# mote_cc3200v7.net
KiCad netlist of a schematic drawn in EAGLE
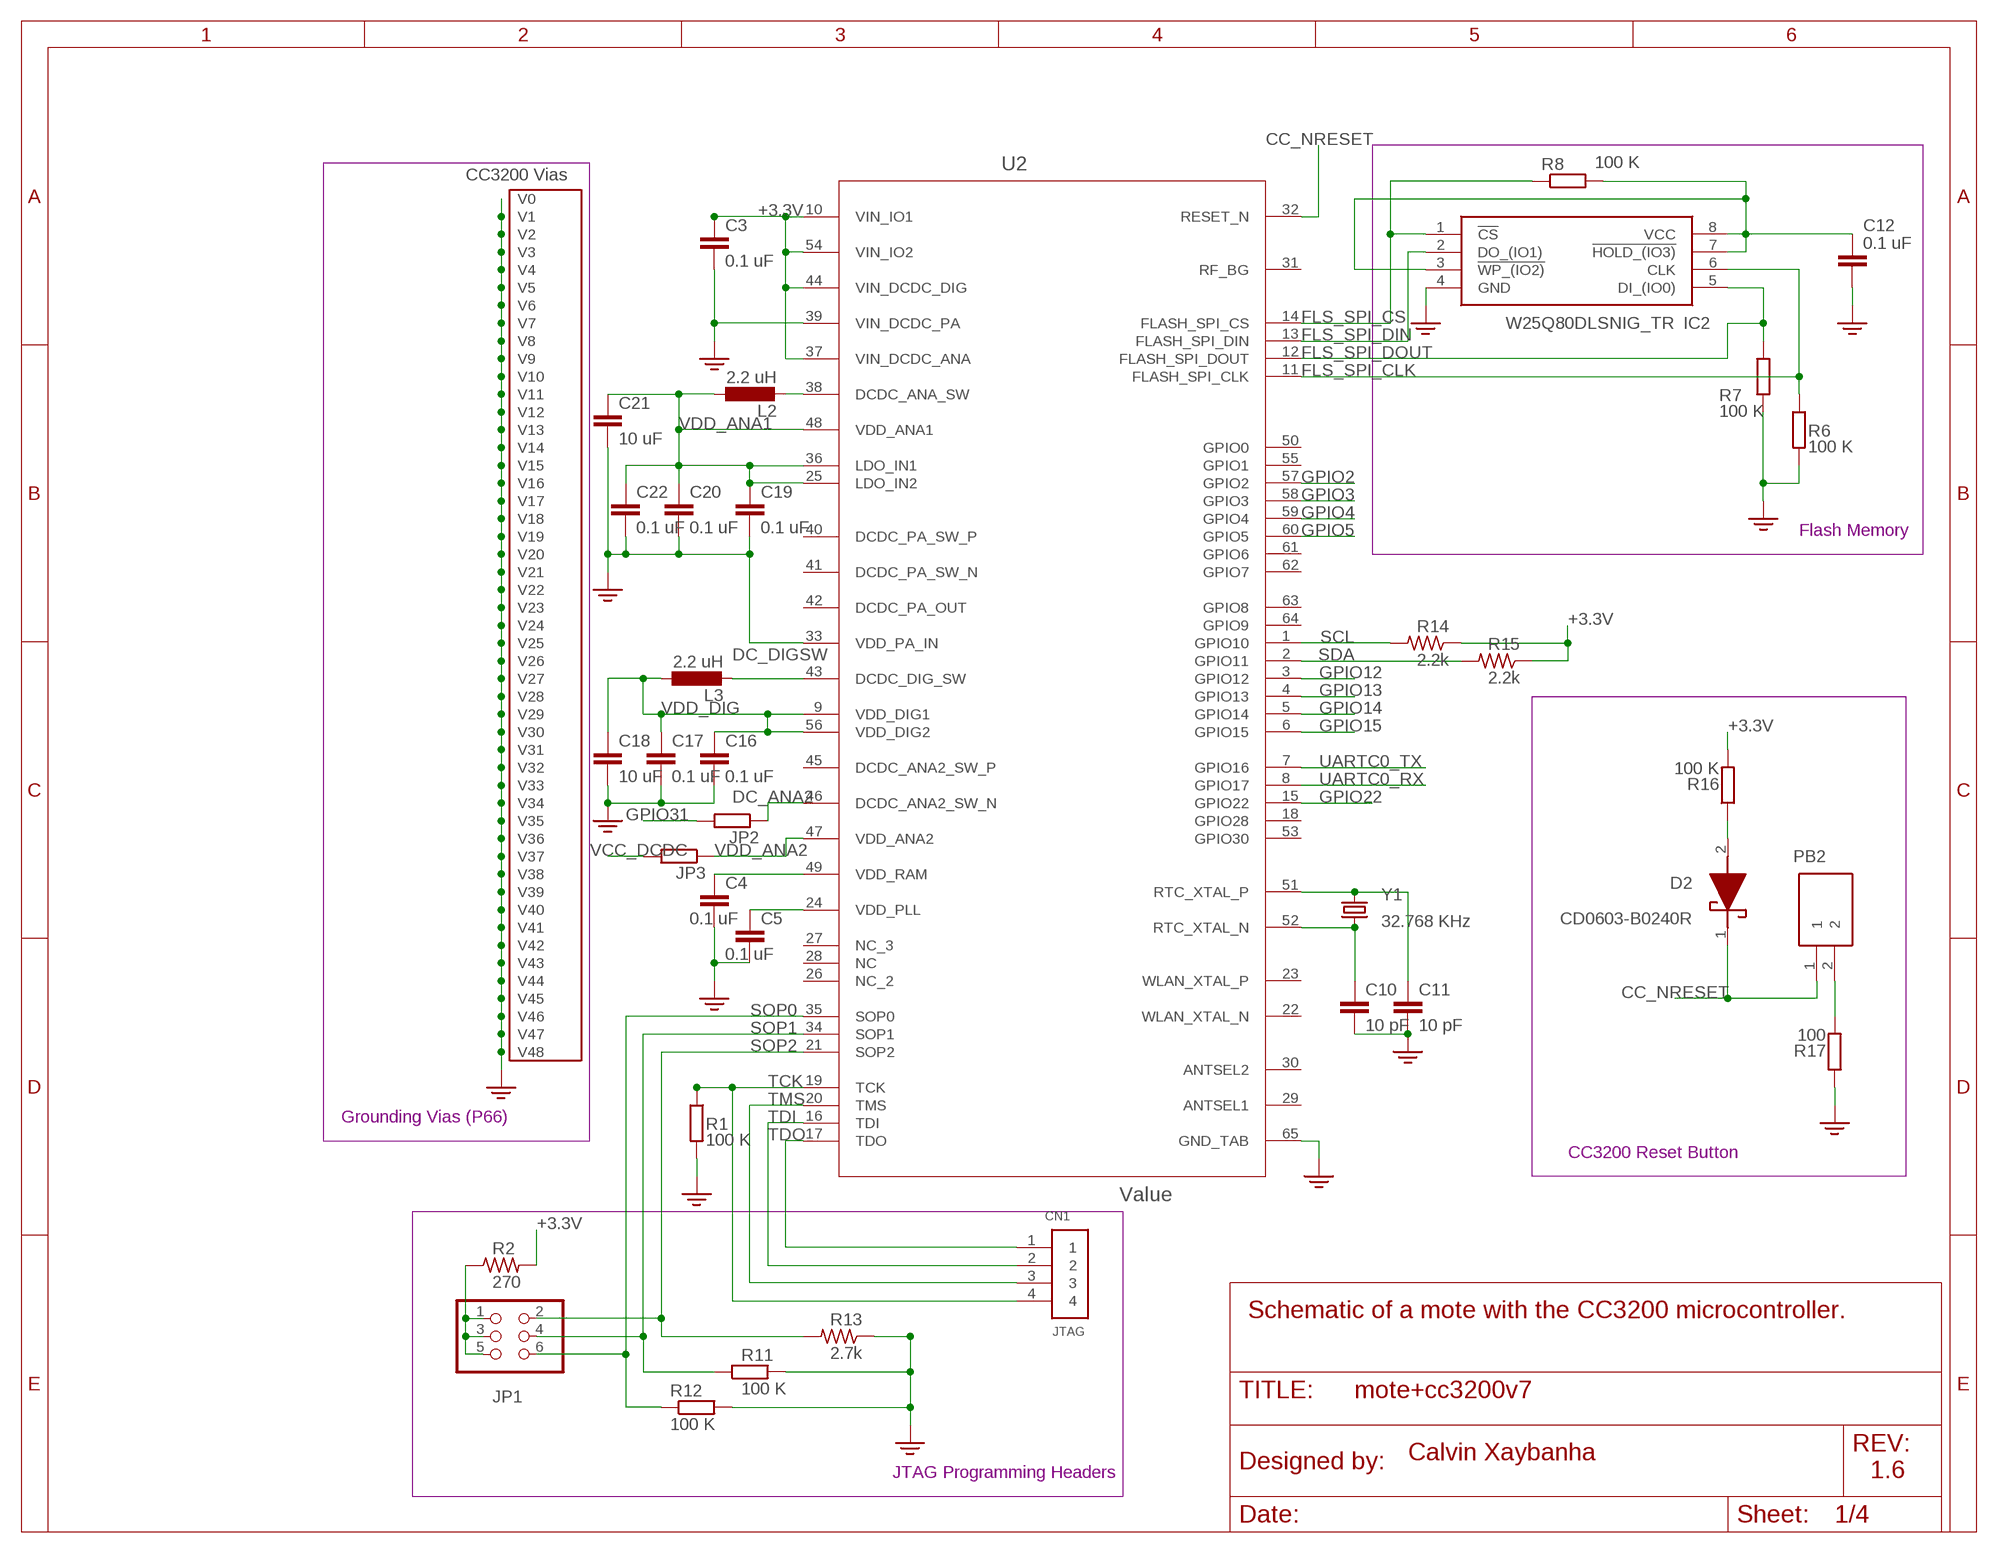
[diagram p0: schematic, sheet 1]
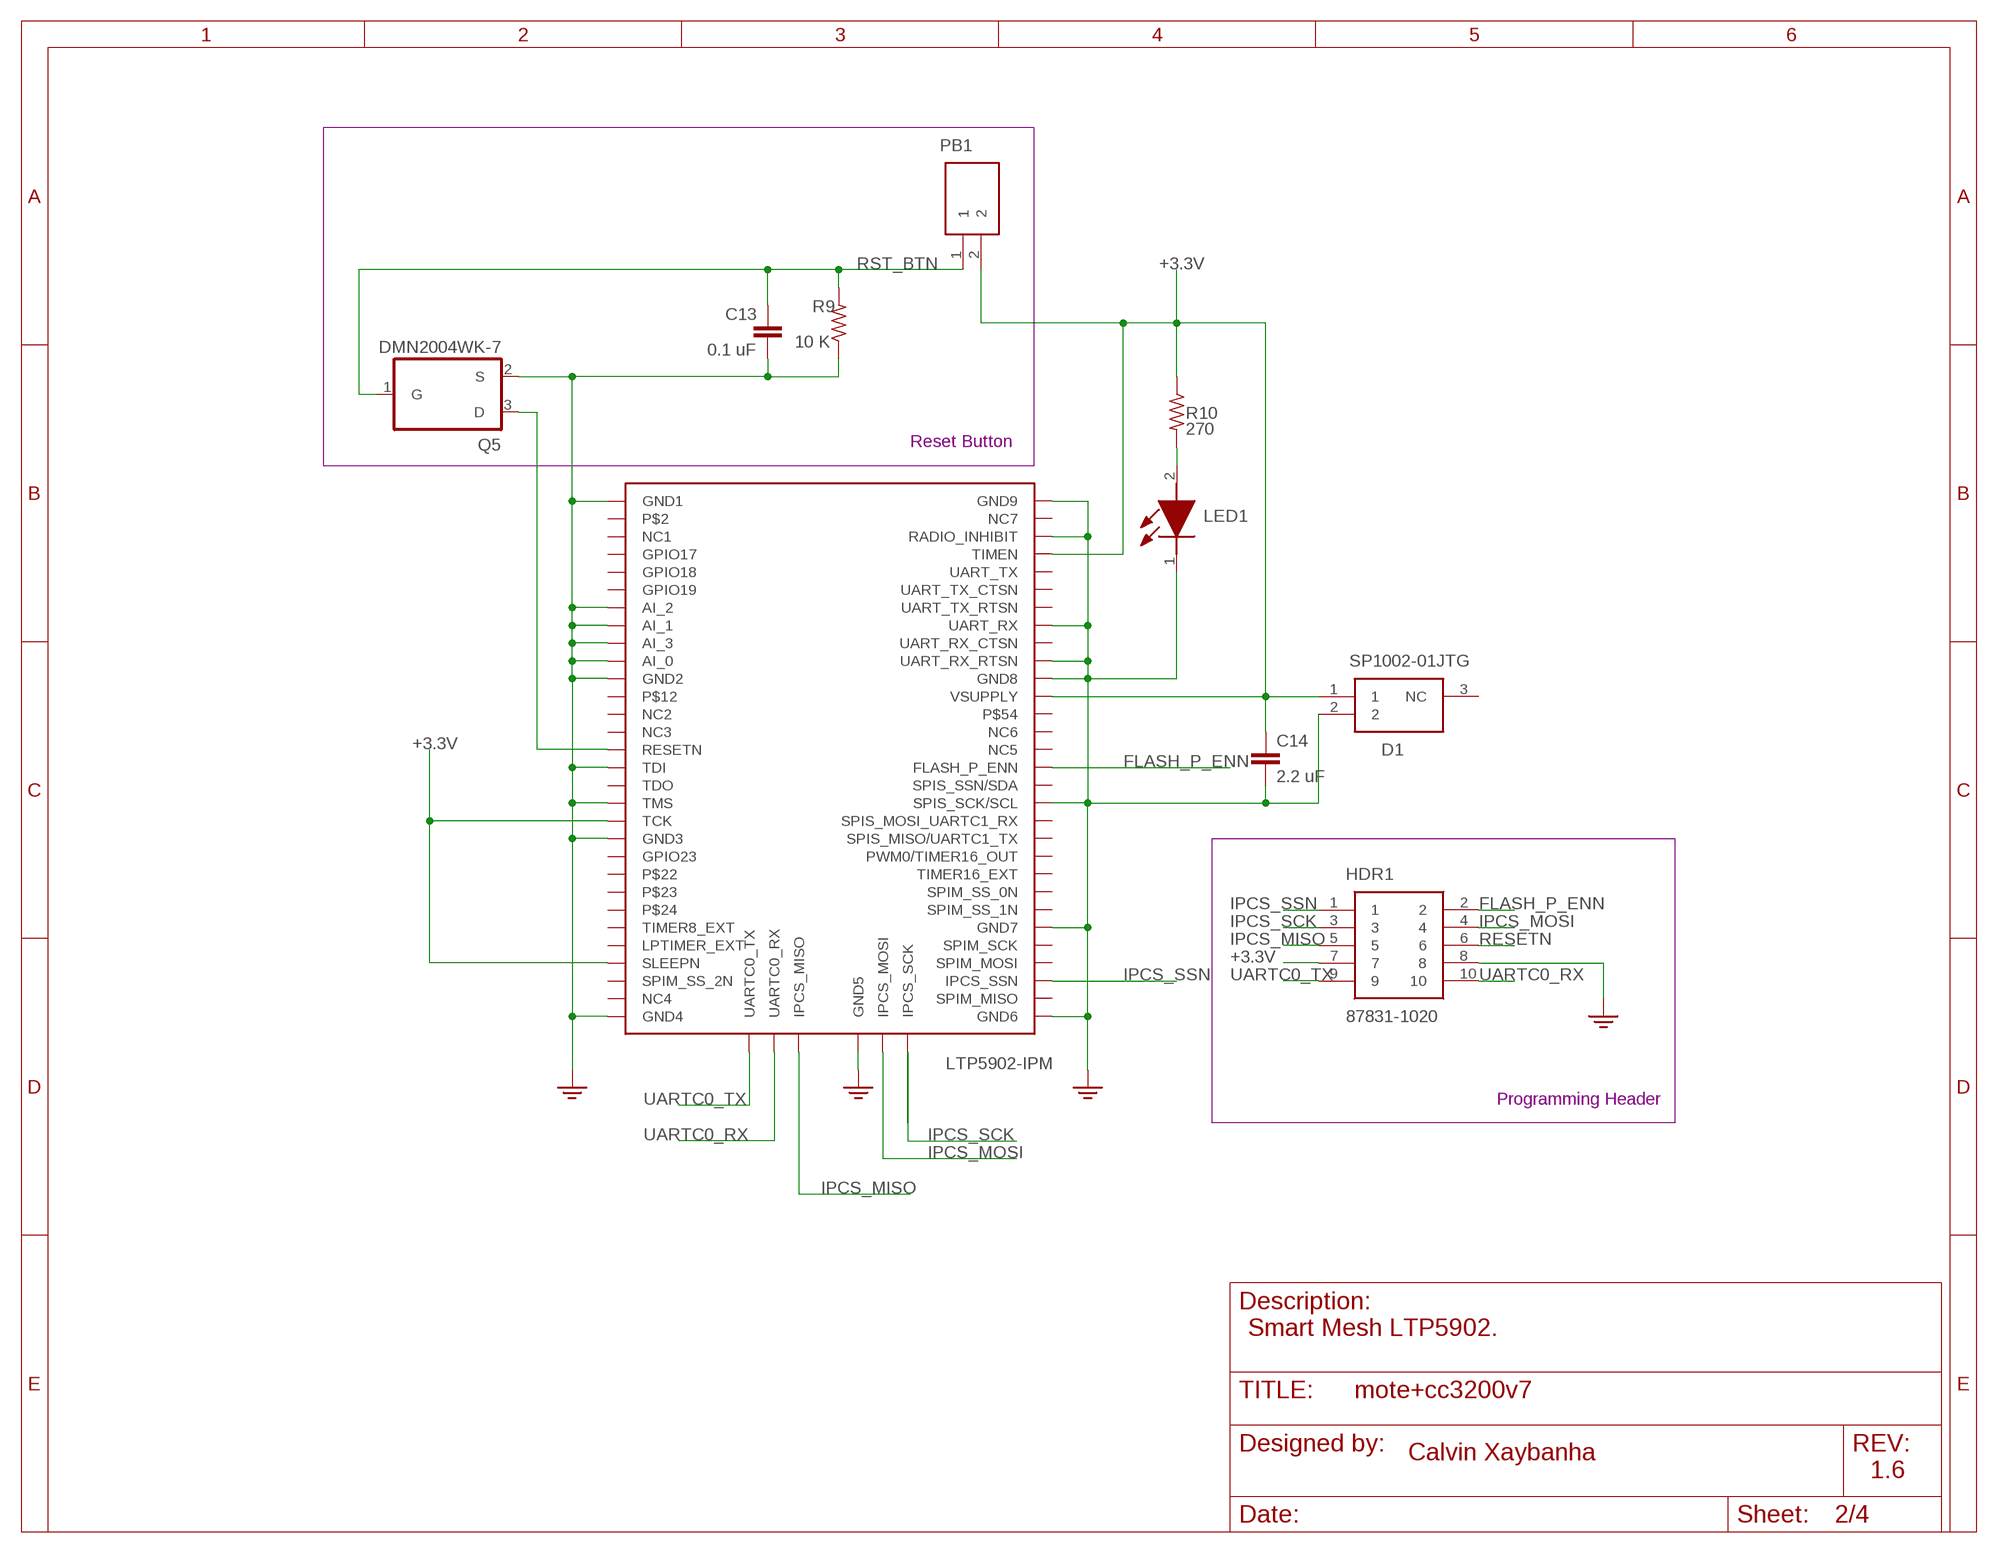
[diagram p1: schematic, sheet 2]
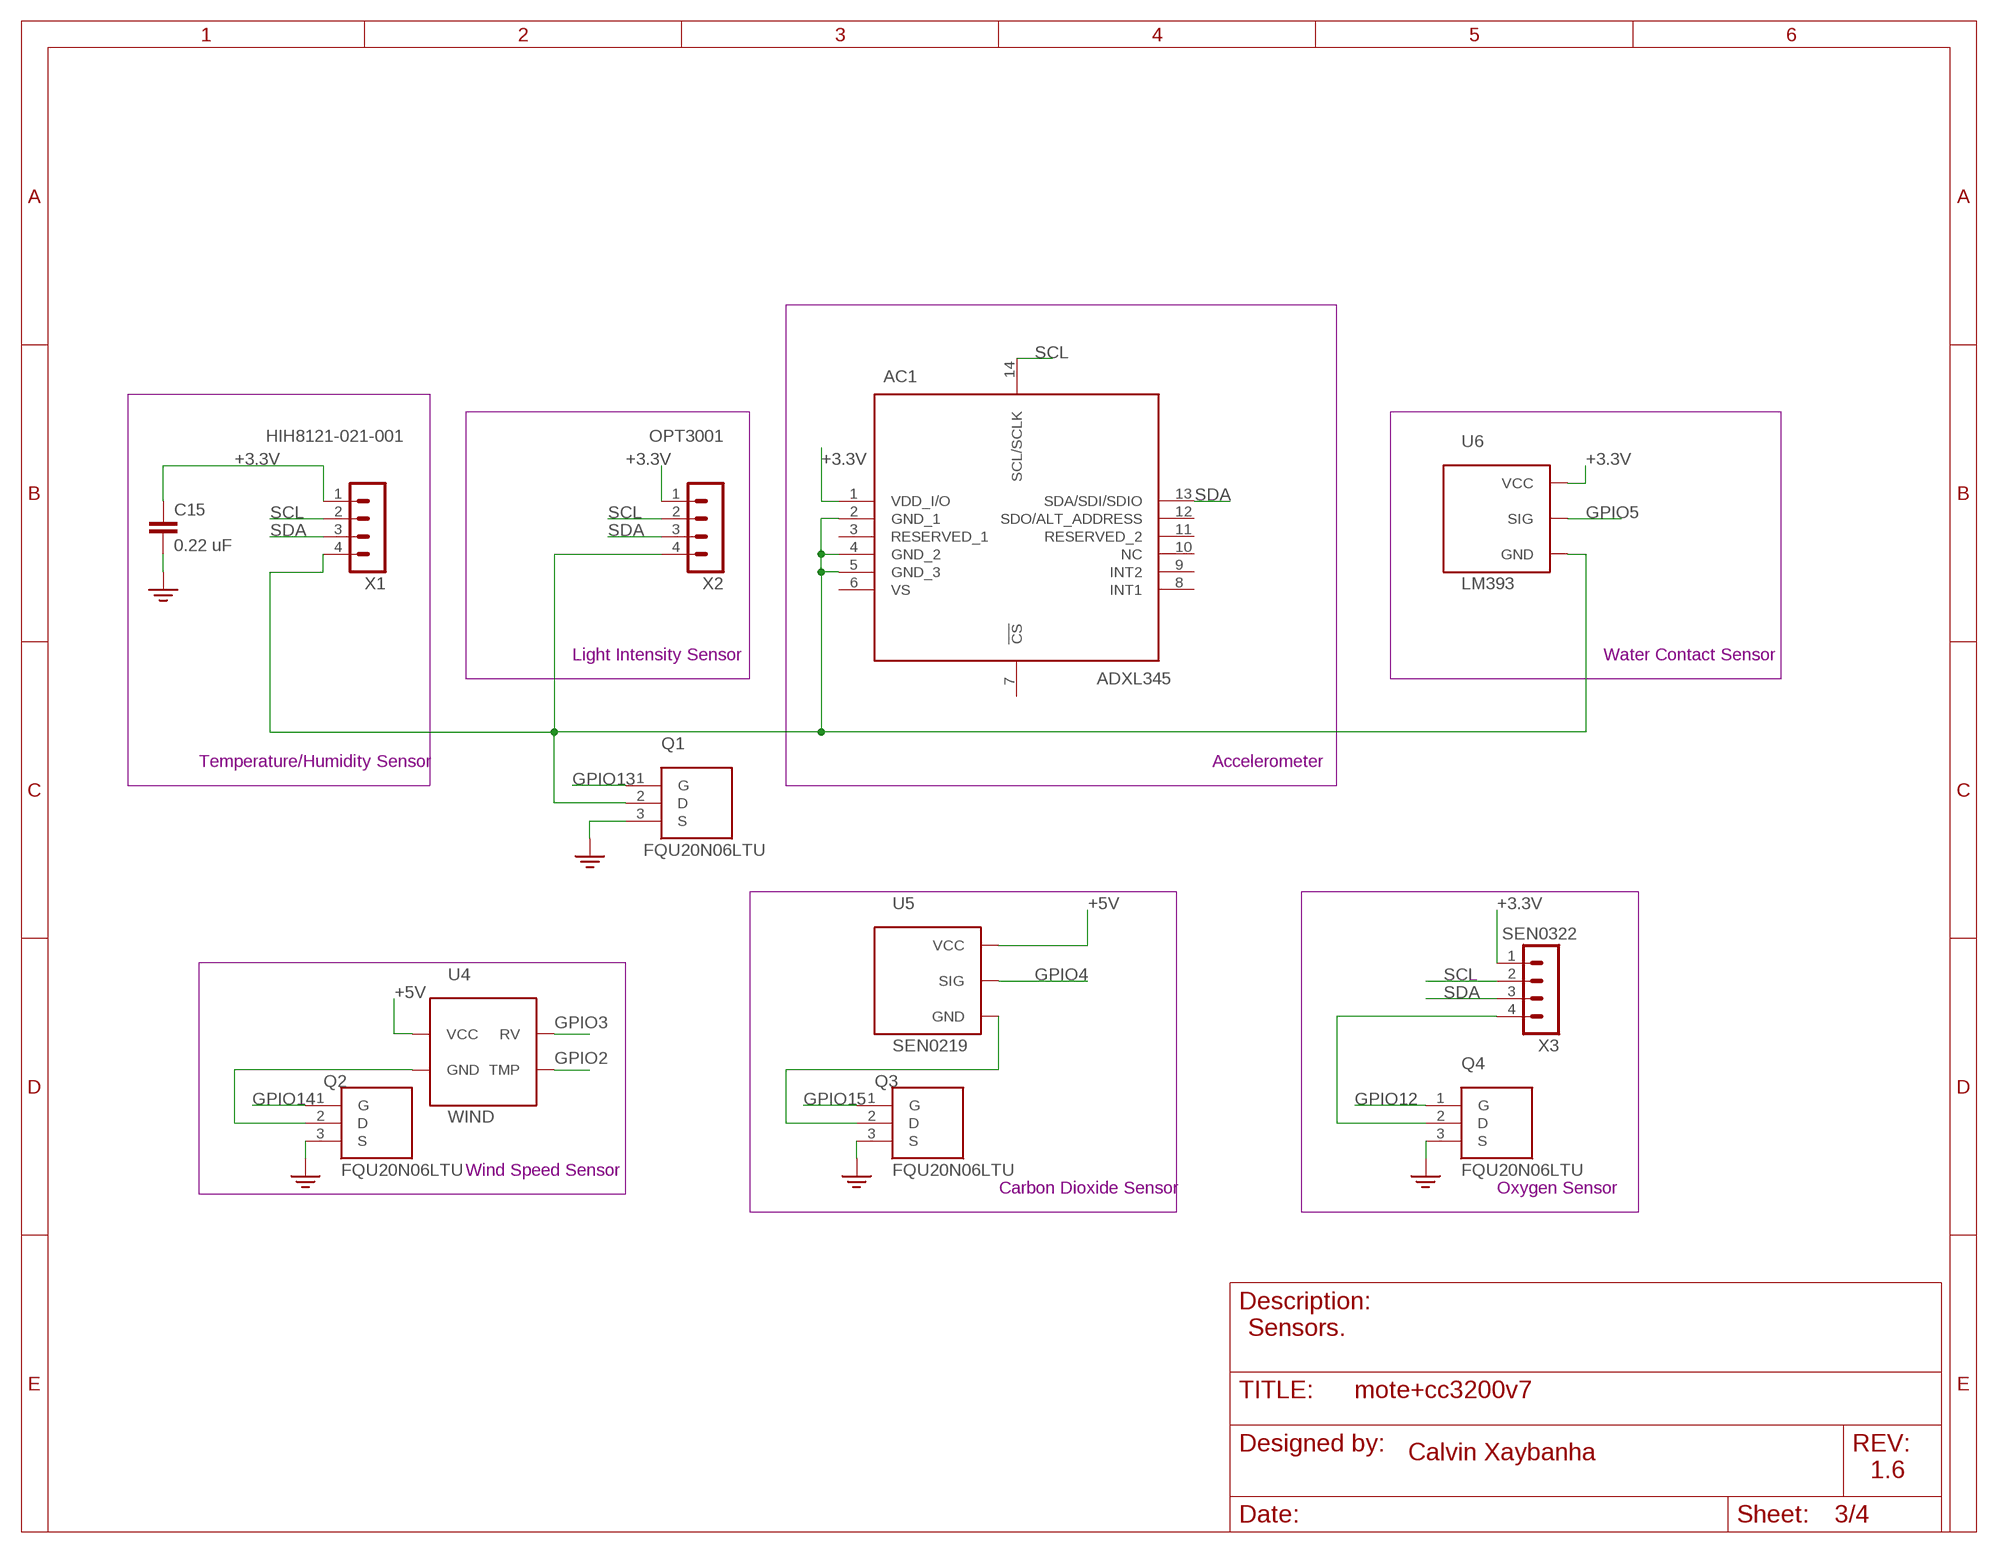
[diagram p2: schematic, sheet 3]
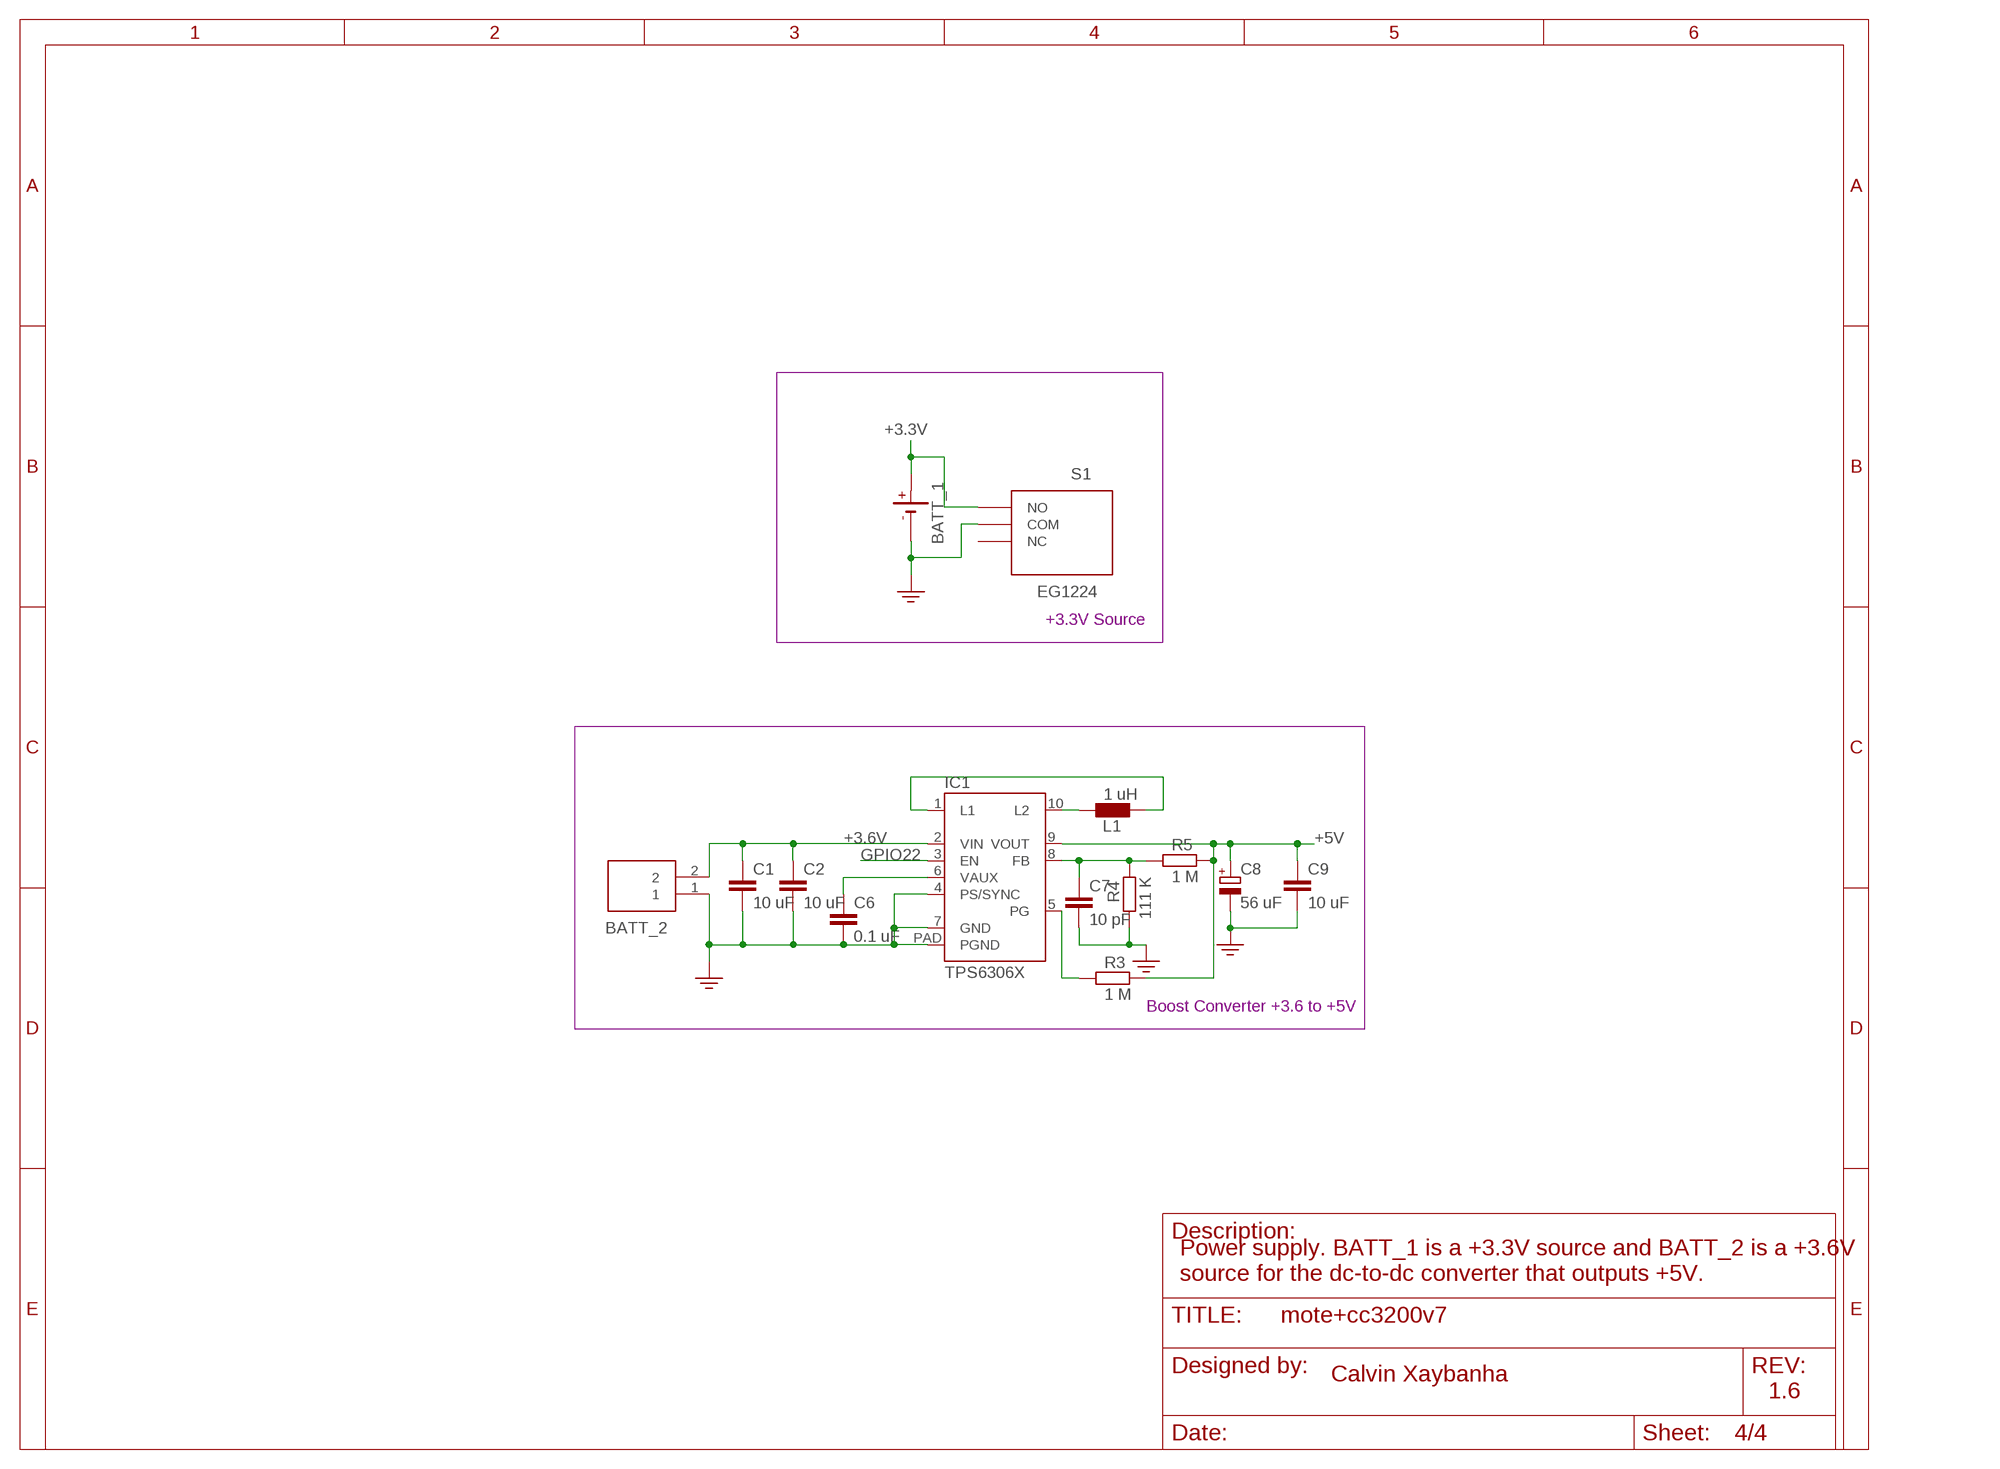
[diagram p3: schematic, sheet 4]

(export (version "E")
  (design (tool "Eeschema 10.0.6"))
  (components
    (comp (ref "AC1")
      (value "ADXL345")
      (footprint "eagle-import:CC-14-1")
      (libsource (lib "eagle-import") (part "ADXL345"))
    )
    (comp (ref "C15")
      (value "0.22 uF")
      (footprint "eagle-import:C5B3.5")
      (libsource (lib "eagle-import") (part "C5/3.5"))
    )
    (comp (ref "Q1")
      (value "FQU20N06LTU")
      (footprint "eagle-import:TO229P250X658X985-3P")
      (fields (field (name "MOUSER_PART_NUMBER") "512-FQU20N06LTU"))
      (libsource (lib "eagle-import") (part "FQU20N06LTU"))
    )
    (comp (ref "Q2")
      (value "FQU20N06LTU")
      (footprint "eagle-import:TO229P250X658X985-3P")
      (fields (field (name "MOUSER_PART_NUMBER") "512-FQU20N06LTU"))
      (libsource (lib "eagle-import") (part "FQU20N06LTU"))
    )
    (comp (ref "Q3")
      (value "FQU20N06LTU")
      (footprint "eagle-import:TO229P250X658X985-3P")
      (fields (field (name "MOUSER_PART_NUMBER") "512-FQU20N06LTU"))
      (libsource (lib "eagle-import") (part "FQU20N06LTU"))
    )
    (comp (ref "Q4")
      (value "FQU20N06LTU")
      (footprint "eagle-import:TO229P250X658X985-3P")
      (fields (field (name "MOUSER_PART_NUMBER") "512-FQU20N06LTU"))
      (libsource (lib "eagle-import") (part "FQU20N06LTU"))
    )
    (comp (ref "U4")
      (value "WIND")
      (footprint "eagle-import:WIND")
      (libsource (lib "eagle-import") (part "WIND"))
    )
    (comp (ref "U5")
      (value "SEN0219")
      (footprint "eagle-import:SEN0219")
      (libsource (lib "eagle-import") (part "SEN0219"))
    )
    (comp (ref "U6")
      (value "LM393")
      (footprint "eagle-import:LM393")
      (libsource (lib "eagle-import") (part "LM393"))
    )
    (comp (ref "X1")
      (value "HIH8121-021-001")
      (footprint "eagle-import:B4B-PH-K-S")
      (libsource (lib "eagle-import") (part "B4B-PH-K-S"))
    )
    (comp (ref "X2")
      (value "OPT3001")
      (footprint "eagle-import:B4B-PH-K-S")
      (libsource (lib "eagle-import") (part "B4B-PH-K-S"))
    )
    (comp (ref "X3")
      (value "SEN0322")
      (footprint "eagle-import:B4B-PH-K-S")
      (libsource (lib "eagle-import") (part "B4B-PH-K-S"))
    )
    (comp (ref "C13")
      (value "0.1 uF")
      (footprint "eagle-import:C1808")
      (libsource (lib "eagle-import") (part "C-EUC1808"))
    )
    (comp (ref "C14")
      (value "2.2 uF")
      (footprint "eagle-import:C1808")
      (libsource (lib "eagle-import") (part "CC1808"))
    )
    (comp (ref "D1")
      (value "SP1002-01JTG")
      (footprint "eagle-import:SOT132P220X110-3N")
      (fields (field (name "MOUSER_PART_NUMBER") "576-SP1002-01JTG"))
      (libsource (lib "eagle-import") (part "SP1002-01JTG"))
    )
    (comp (ref "HDR1")
      (value "87831-1020")
      (footprint "eagle-import:SHDR10W55P200_2X5_1265X630X640")
      (fields (field (name "MOUSER_PART_NUMBER") "538-87831-1020"))
      (libsource (lib "eagle-import") (part "87831-1020"))
    )
    (comp (ref "LED1")
      (value "156120RS75000")
      (footprint "eagle-import:LEDM3216X130N")
      (fields (field (name "MOUSER_PART_NUMBER") "710-156120RS75000"))
      (libsource (lib "eagle-import") (part "156120RS75000"))
    )
    (comp (ref "PB1")
      (value "FSMSM")
      (footprint "eagle-import:FSMSM")
      (fields (field (name "MOUSER_PART_NUMBER") "506-FSMSM"))
      (libsource (lib "eagle-import") (part "FSMSM"))
    )
    (comp (ref "Q5")
      (value "DMN2004WK-7")
      (footprint "eagle-import:SC70-3_DCK")
      (libsource (lib "eagle-import") (part "DMN2004WK-7"))
    )
    (comp (ref "R9")
      (value "10 K")
      (footprint "eagle-import:RES_1206")
      (fields
        (field (name "DIGIKEY_PART_NUMBER") "WSLP-.05TR-ND")
        (field (name "MANUFACTURER") "Vishay Dale")
        (field (name "MPN") "WSLP1206R0500FEA")
        (field (name "CREATED_BY") "PCBLayout.com")
      )
      (libsource (lib "eagle-import") (part "WSLP1206R0500FEA"))
    )
    (comp (ref "R10")
      (value "270")
      (footprint "eagle-import:RES_1206")
      (fields
        (field (name "DIGIKEY_PART_NUMBER") "WSLP-.05TR-ND")
        (field (name "MANUFACTURER") "Vishay Dale")
        (field (name "MPN") "WSLP1206R0500FEA")
        (field (name "CREATED_BY") "PCBLayout.com")
      )
      (libsource (lib "eagle-import") (part "WSLP1206R0500FEA"))
    )
    (comp (ref "U3")
      (value "LTP5902")
      (footprint "eagle-import:LTP5902-MMCX")
      (libsource (lib "eagle-import") (part "LTP5902"))
    )
    (comp (ref "C3")
      (value "0.1 uF")
      (footprint "eagle-import:C1808")
      (libsource (lib "eagle-import") (part "C-EUC1808"))
    )
    (comp (ref "C4")
      (value "0.1 uF")
      (footprint "eagle-import:C1808")
      (libsource (lib "eagle-import") (part "C-EUC1808"))
    )
    (comp (ref "C5")
      (value "0.1 uF")
      (footprint "eagle-import:C1808")
      (libsource (lib "eagle-import") (part "C-EUC1808"))
    )
    (comp (ref "C10")
      (value "10 pF")
      (footprint "eagle-import:C1808")
      (libsource (lib "eagle-import") (part "CC1808"))
    )
    (comp (ref "C11")
      (value "10 pF")
      (footprint "eagle-import:C1808")
      (libsource (lib "eagle-import") (part "CC1808"))
    )
    (comp (ref "C12")
      (value "0.1 uF")
      (footprint "eagle-import:C1808")
      (libsource (lib "eagle-import") (part "C-EUC1808"))
    )
    (comp (ref "C16")
      (value "0.1 uF")
      (footprint "eagle-import:C1808")
      (libsource (lib "eagle-import") (part "C-EUC1808"))
    )
    (comp (ref "C17")
      (value "0.1 uF")
      (footprint "eagle-import:C1808")
      (libsource (lib "eagle-import") (part "C-EUC1808"))
    )
    (comp (ref "C18")
      (value "10 uF")
      (footprint "eagle-import:C1808")
      (libsource (lib "eagle-import") (part "CC1808"))
    )
    (comp (ref "C19")
      (value "0.1 uF")
      (footprint "eagle-import:C1808")
      (libsource (lib "eagle-import") (part "C-EUC1808"))
    )
    (comp (ref "C20")
      (value "0.1 uF")
      (footprint "eagle-import:C1808")
      (libsource (lib "eagle-import") (part "C-EUC1808"))
    )
    (comp (ref "C21")
      (value "10 uF")
      (footprint "eagle-import:C1808")
      (libsource (lib "eagle-import") (part "CC1808"))
    )
    (comp (ref "C22")
      (value "0.1 uF")
      (footprint "eagle-import:C1808")
      (libsource (lib "eagle-import") (part "C-EUC1808"))
    )
    (comp (ref "CN1")
      (value "JTAG")
      (footprint "eagle-import:1X04-BIG")
      (libsource (lib "eagle-import") (part "1X4-BIG"))
    )
    (comp (ref "D2")
      (value "CD0603-B0240R")
      (footprint "eagle-import:CD0603B0240R")
      (fields (field (name "MOUSER_PART_NUMBER") "652-CD0603-B0240R"))
      (libsource (lib "eagle-import") (part "CD0603-B0240R"))
    )
    (comp (ref "IC2")
      (value "W25Q80DLSNIG_TR")
      (footprint "eagle-import:SOIC127P600X175-8N")
      (fields
        (field (name "MANUFACTURER_PART_NUMBER") "W25Q80DLSNIG TR")
        (field (name "MOUSER_PART_NUMBER") "454-W25Q80DLSNIGTR")
      )
      (libsource (lib "eagle-import") (part "W25Q80DLSNIG_TR"))
    )
    (comp (ref "JP1")
      (value "PINHD-2X3/90")
      (footprint "eagle-import:2X03_90")
      (libsource (lib "eagle-import") (part "PINHD-2X3/90"))
    )
    (comp (ref "JP2")
      (value "RR0201")
      (footprint "eagle-import:R0201")
      (libsource (lib "eagle-import") (part "RR0201"))
    )
    (comp (ref "JP3")
      (value "RR0201")
      (footprint "eagle-import:R0201")
      (libsource (lib "eagle-import") (part "RR0201"))
    )
    (comp (ref "L2")
      (value "2.2 uH")
      (footprint "eagle-import:L3216C")
      (libsource (lib "eagle-import") (part "L-EUL3216C"))
    )
    (comp (ref "L3")
      (value "2.2 uH")
      (footprint "eagle-import:L3216C")
      (libsource (lib "eagle-import") (part "L-EUL3216C"))
    )
    (comp (ref "PB2")
      (value "FSMSM")
      (footprint "eagle-import:FSMSM")
      (fields (field (name "MOUSER_PART_NUMBER") "506-FSMSM"))
      (libsource (lib "eagle-import") (part "FSMSM"))
    )
    (comp (ref "R1")
      (value "100 K")
      (footprint "eagle-import:R1206")
      (libsource (lib "eagle-import") (part "R-EU_R1206"))
    )
    (comp (ref "R2")
      (value "270")
      (footprint "eagle-import:RES_1206")
      (fields
        (field (name "DIGIKEY_PART_NUMBER") "WSLP-.05TR-ND")
        (field (name "MANUFACTURER") "Vishay Dale")
        (field (name "MPN") "WSLP1206R0500FEA")
        (field (name "CREATED_BY") "PCBLayout.com")
      )
      (libsource (lib "eagle-import") (part "WSLP1206R0500FEA"))
    )
    (comp (ref "R6")
      (value "100 K")
      (footprint "eagle-import:R1206")
      (libsource (lib "eagle-import") (part "R-EU_R1206"))
    )
    (comp (ref "R7")
      (value "100 K")
      (footprint "eagle-import:R1206")
      (libsource (lib "eagle-import") (part "R-EU_R1206"))
    )
    (comp (ref "R8")
      (value "100 K")
      (footprint "eagle-import:R1206")
      (libsource (lib "eagle-import") (part "R-EU_R1206"))
    )
    (comp (ref "R11")
      (value "100 K")
      (footprint "eagle-import:R1206")
      (libsource (lib "eagle-import") (part "R-EU_R1206"))
    )
    (comp (ref "R12")
      (value "100 K")
      (footprint "eagle-import:R1206")
      (libsource (lib "eagle-import") (part "R-EU_R1206"))
    )
    (comp (ref "R13")
      (value "2.7k")
      (footprint "eagle-import:RES_1206")
      (fields
        (field (name "DIGIKEY_PART_NUMBER") "WSLP-.05TR-ND")
        (field (name "MANUFACTURER") "Vishay Dale")
        (field (name "MPN") "WSLP1206R0500FEA")
        (field (name "CREATED_BY") "PCBLayout.com")
      )
      (libsource (lib "eagle-import") (part "WSLP1206R0500FEA"))
    )
    (comp (ref "R14")
      (value "2.2k")
      (footprint "eagle-import:RES_1206")
      (fields
        (field (name "DIGIKEY_PART_NUMBER") "WSLP-.05TR-ND")
        (field (name "MANUFACTURER") "Vishay Dale")
        (field (name "MPN") "WSLP1206R0500FEA")
        (field (name "CREATED_BY") "PCBLayout.com")
      )
      (libsource (lib "eagle-import") (part "WSLP1206R0500FEA"))
    )
    (comp (ref "R15")
      (value "2.2k")
      (footprint "eagle-import:RES_1206")
      (fields
        (field (name "DIGIKEY_PART_NUMBER") "WSLP-.05TR-ND")
        (field (name "MANUFACTURER") "Vishay Dale")
        (field (name "MPN") "WSLP1206R0500FEA")
        (field (name "CREATED_BY") "PCBLayout.com")
      )
      (libsource (lib "eagle-import") (part "WSLP1206R0500FEA"))
    )
    (comp (ref "R16")
      (value "100 K")
      (footprint "eagle-import:R1206")
      (libsource (lib "eagle-import") (part "R-EU_R1206"))
    )
    (comp (ref "R17")
      (value "100")
      (footprint "eagle-import:R1206")
      (libsource (lib "eagle-import") (part "R-EU_R1206"))
    )
    (comp (ref "U2")
      (value "Value")
      (footprint "eagle-import:RGC0064A")
      (fields
        (field (name "ALTERNATEPARTNUMBER") "CC3200R1M2RGC")
        (field (name "MANUFACTURER") "Texas Instruments")
        (field (name "PARTNUMBER") "CC3200R1M2RGCR")
      )
      (libsource (lib "eagle-import") (part "CC3200R1M2RGCR"))
    )
    (comp (ref "Y1")
      (value "32.768 KHz")
      (footprint "eagle-import:7.0X5.0")
      (libsource (lib "eagle-import") (part "KX-13"))
    )
    (comp (ref "BATT_1")
      (value "BATTERY_BR1225/FA")
      (footprint "eagle-import:BATTERY_BR1225_FA")
      (libsource (lib "eagle-import") (part "BATTERY_BR1225/FA"))
    )
    (comp (ref "BATT_2")
      (value "12BH23P-GR")
      (footprint "eagle-import:12BH23PGR")
      (libsource (lib "eagle-import") (part "12BH23P-GR"))
    )
    (comp (ref "C1")
      (value "10 uF")
      (footprint "eagle-import:C1808")
      (libsource (lib "eagle-import") (part "CC1808"))
    )
    (comp (ref "C2")
      (value "10 uF")
      (footprint "eagle-import:C1808")
      (libsource (lib "eagle-import") (part "CC1808"))
    )
    (comp (ref "C6")
      (value "0.1 uF")
      (footprint "eagle-import:C1808")
      (libsource (lib "eagle-import") (part "C-EUC1808"))
    )
    (comp (ref "C7")
      (value "10 pF")
      (footprint "eagle-import:C1808")
      (libsource (lib "eagle-import") (part "CC1808"))
    )
    (comp (ref "C8")
      (value "56 uF")
      (footprint "eagle-import:E3,5-8")
      (libsource (lib "eagle-import") (part "CPOL-EUE3.5-8"))
    )
    (comp (ref "C9")
      (value "10 uF")
      (footprint "eagle-import:C1808")
      (libsource (lib "eagle-import") (part "CC1808"))
    )
    (comp (ref "IC1")
      (value "TPS6306X")
      (footprint "eagle-import:S-PWSON-N10")
      (libsource (lib "eagle-import") (part "TPS6306X"))
    )
    (comp (ref "L1")
      (value "1 uH")
      (footprint "eagle-import:0204_7")
      (libsource (lib "eagle-import") (part "L0204/7"))
    )
    (comp (ref "R3")
      (value "1 M")
      (footprint "eagle-import:R5025")
      (libsource (lib "eagle-import") (part "R-EU_R5025"))
    )
    (comp (ref "R4")
      (value "111 K")
      (footprint "eagle-import:R1206")
      (libsource (lib "eagle-import") (part "R-EU_R1206"))
    )
    (comp (ref "R5")
      (value "1 M")
      (footprint "eagle-import:R5025")
      (libsource (lib "eagle-import") (part "R-EU_R5025"))
    )
    (comp (ref "S1")
      (value "EG1224")
      (footprint "eagle-import:EG1224")
      (fields (field (name "MOUSER_PART_NUMBER") "612-EG1224"))
      (libsource (lib "eagle-import") (part "EG1224"))
    )
  )
  (nets
    (net (code "1") (name "+3.3V") (class "Default")
      (node (ref "AC1") (pin "1") (pinfunction "VDD_I/O_1") (pintype "power_in"))
      (node (ref "BATT_1") (pin "+") (pinfunction "+_+") (pintype "passive"))
      (node (ref "C12") (pin "1") (pinfunction "1_1") (pintype "passive"))
      (node (ref "C14") (pin "1") (pinfunction "1_1") (pintype "passive"))
      (node (ref "C15") (pin "1") (pinfunction "1_1") (pintype "passive"))
      (node (ref "C3") (pin "1") (pinfunction "1_1") (pintype "passive"))
      (node (ref "D1") (pin "1") (pinfunction "1_1") (pintype "bidirectional"))
      (node (ref "HDR1") (pin "7") (pinfunction "7_7") (pintype "bidirectional"))
      (node (ref "IC2") (pin "3") (pinfunction "~{WP_(IO2})_3") (pintype "bidirectional"))
      (node (ref "IC2") (pin "7") (pinfunction "~{HOLD_(IO3})_7") (pintype "bidirectional"))
      (node (ref "IC2") (pin "8") (pinfunction "VCC_8") (pintype "bidirectional"))
      (node (ref "PB1") (pin "2") (pinfunction "2_2") (pintype "bidirectional"))
      (node (ref "R10") (pin "1") (pinfunction "1_1") (pintype "passive"))
      (node (ref "R14") (pin "1") (pinfunction "1_1") (pintype "passive"))
      (node (ref "R15") (pin "1") (pinfunction "1_1") (pintype "passive"))
      (node (ref "R16") (pin "2") (pinfunction "2_2") (pintype "passive"))
      (node (ref "R2") (pin "2") (pinfunction "2_2") (pintype "passive"))
      (node (ref "R8") (pin "2") (pinfunction "2_2") (pintype "passive"))
      (node (ref "S1") (pin "1") (pinfunction "NO_1") (pintype "bidirectional"))
      (node (ref "U2") (pin "10") (pinfunction "VIN_IO1_10") (pintype "power_in"))
      (node (ref "U2") (pin "37") (pinfunction "VIN_DCDC_ANA_37") (pintype "power_in"))
      (node (ref "U2") (pin "44") (pinfunction "VIN_DCDC_DIG_44") (pintype "power_in"))
      (node (ref "U2") (pin "54") (pinfunction "VIN_IO2_54") (pintype "power_in"))
      (node (ref "U3") (pin "P19") (pinfunction "TCK_P19") (pintype "bidirectional"))
      (node (ref "U3") (pin "P27") (pinfunction "SLEEPN_P27") (pintype "bidirectional"))
      (node (ref "U3") (pin "P55") (pinfunction "VSUPPLY_P55") (pintype "bidirectional"))
      (node (ref "U3") (pin "P63") (pinfunction "TIMEN_P63") (pintype "bidirectional"))
      (node (ref "U6") (pin "P$1") (pinfunction "VCC_P$1") (pintype "power_in"))
      (node (ref "X1") (pin "1") (pinfunction "1_1") (pintype "power_in"))
      (node (ref "X2") (pin "1") (pinfunction "1_1") (pintype "power_in"))
      (node (ref "X3") (pin "1") (pinfunction "1_1") (pintype "power_in"))
    )
    (net (code "2") (name "+3.6V") (class "Default")
      (node (ref "BATT_2") (pin "2") (pinfunction "2_2") (pintype "bidirectional"))
      (node (ref "C1") (pin "1") (pinfunction "1_1") (pintype "passive"))
      (node (ref "C2") (pin "1") (pinfunction "1_1") (pintype "passive"))
      (node (ref "IC1") (pin "2") (pinfunction "VIN_2") (pintype "passive"))
    )
    (net (code "3") (name "+5V") (class "Default")
      (node (ref "C8") (pin "+") (pinfunction "+_+") (pintype "passive"))
      (node (ref "C9") (pin "1") (pinfunction "1_1") (pintype "passive"))
      (node (ref "IC1") (pin "9") (pinfunction "VOUT_9") (pintype "passive"))
      (node (ref "R3") (pin "2") (pinfunction "2_2") (pintype "passive"))
      (node (ref "R5") (pin "2") (pinfunction "2_2") (pintype "passive"))
      (node (ref "U4") (pin "P$1") (pinfunction "VCC_P$1") (pintype "power_in"))
      (node (ref "U5") (pin "P$1") (pinfunction "VCC_P$1") (pintype "power_in"))
    )
    (net (code "4") (name "CC_NRESET") (class "Default")
      (node (ref "D2") (pin "1") (pinfunction "K_1") (pintype "bidirectional"))
      (node (ref "PB2") (pin "1") (pinfunction "1_1") (pintype "bidirectional"))
      (node (ref "U2") (pin "32") (pinfunction "RESET_N_32") (pintype "input"))
    )
    (net (code "5") (name "DCDC_PA_OUT") (class "Default")
      (node (ref "U2") (pin "42") (pinfunction "DCDC_PA_OUT_42") (pintype "power_in"))
    )
    (net (code "6") (name "DCDC_PA_SW_N") (class "Default")
      (node (ref "U2") (pin "41") (pinfunction "DCDC_PA_SW_N_41") (pintype "power_in"))
    )
    (net (code "7") (name "DCDC_PA_SW_P") (class "Default")
      (node (ref "U2") (pin "40") (pinfunction "DCDC_PA_SW_P_40") (pintype "power_in"))
    )
    (net (code "8") (name "DC_ANA2") (class "Default")
      (node (ref "JP2") (pin "1") (pinfunction "1_1") (pintype "passive"))
      (node (ref "U2") (pin "46") (pinfunction "DCDC_ANA2_SW_N_46") (pintype "bidirectional"))
    )
    (net (code "9") (name "DC_DIGSW") (class "Default")
      (node (ref "L3") (pin "2") (pinfunction "2_2") (pintype "passive"))
      (node (ref "U2") (pin "43") (pinfunction "DCDC_DIG_SW_43") (pintype "power_in"))
    )
    (net (code "10") (name "FLASH_P_ENN") (class "Default")
      (node (ref "HDR1") (pin "2") (pinfunction "2_2") (pintype "bidirectional"))
      (node (ref "U3") (pin "P51") (pinfunction "FLASH_P_ENN_P51") (pintype "bidirectional"))
    )
    (net (code "11") (name "FLS_SPI_CLK") (class "Default")
      (node (ref "IC2") (pin "6") (pinfunction "CLK_6") (pintype "bidirectional"))
      (node (ref "R6") (pin "1") (pinfunction "1_1") (pintype "passive"))
      (node (ref "U2") (pin "11") (pinfunction "FLASH_SPI_CLK_11") (pintype "output"))
    )
    (net (code "12") (name "FLS_SPI_CS") (class "Default")
      (node (ref "IC2") (pin "1") (pinfunction "~{CS}_1") (pintype "bidirectional"))
      (node (ref "R8") (pin "1") (pinfunction "1_1") (pintype "passive"))
      (node (ref "U2") (pin "14") (pinfunction "FLASH_SPI_CS_14") (pintype "output"))
    )
    (net (code "13") (name "FLS_SPI_DIN") (class "Default")
      (node (ref "IC2") (pin "2") (pinfunction "DO_(IO1)_2") (pintype "bidirectional"))
      (node (ref "U2") (pin "13") (pinfunction "FLASH_SPI_DIN_13") (pintype "input"))
    )
    (net (code "14") (name "FLS_SPI_DOUT") (class "Default")
      (node (ref "IC2") (pin "5") (pinfunction "DI_(IO0)_5") (pintype "bidirectional"))
      (node (ref "R7") (pin "1") (pinfunction "1_1") (pintype "passive"))
      (node (ref "U2") (pin "12") (pinfunction "FLASH_SPI_DOUT_12") (pintype "output"))
    )
    (net (code "15") (name "GND") (class "Default")
      (node (ref "BATT_1") (pin "-") (pinfunction "-_-") (pintype "passive"))
      (node (ref "BATT_2") (pin "1") (pinfunction "1_1") (pintype "bidirectional"))
      (node (ref "C1") (pin "2") (pinfunction "2_2") (pintype "passive"))
      (node (ref "C10") (pin "2") (pinfunction "2_2") (pintype "passive"))
      (node (ref "C11") (pin "2") (pinfunction "2_2") (pintype "passive"))
      (node (ref "C12") (pin "2") (pinfunction "2_2") (pintype "passive"))
      (node (ref "C13") (pin "2") (pinfunction "2_2") (pintype "passive"))
      (node (ref "C14") (pin "2") (pinfunction "2_2") (pintype "passive"))
      (node (ref "C15") (pin "2") (pinfunction "2_2") (pintype "passive"))
      (node (ref "C16") (pin "2") (pinfunction "2_2") (pintype "passive"))
      (node (ref "C17") (pin "2") (pinfunction "2_2") (pintype "passive"))
      (node (ref "C18") (pin "2") (pinfunction "2_2") (pintype "passive"))
      (node (ref "C19") (pin "2") (pinfunction "2_2") (pintype "passive"))
      (node (ref "C2") (pin "2") (pinfunction "2_2") (pintype "passive"))
      (node (ref "C20") (pin "2") (pinfunction "2_2") (pintype "passive"))
      (node (ref "C21") (pin "2") (pinfunction "2_2") (pintype "passive"))
      (node (ref "C22") (pin "2") (pinfunction "2_2") (pintype "passive"))
      (node (ref "C3") (pin "2") (pinfunction "2_2") (pintype "passive"))
      (node (ref "C4") (pin "2") (pinfunction "2_2") (pintype "passive"))
      (node (ref "C5") (pin "2") (pinfunction "2_2") (pintype "passive"))
      (node (ref "C6") (pin "2") (pinfunction "2_2") (pintype "passive"))
      (node (ref "C7") (pin "2") (pinfunction "2_2") (pintype "passive"))
      (node (ref "C8") (pin "-") (pinfunction "-_-") (pintype "passive"))
      (node (ref "C9") (pin "2") (pinfunction "2_2") (pintype "passive"))
      (node (ref "D1") (pin "2") (pinfunction "2_2") (pintype "bidirectional"))
      (node (ref "HDR1") (pin "8") (pinfunction "8_8") (pintype "bidirectional"))
      (node (ref "IC1") (pin "4") (pinfunction "PS/SYNC_4") (pintype "passive"))
      (node (ref "IC1") (pin "7") (pinfunction "GND_7") (pintype "passive"))
      (node (ref "IC1") (pin "PAD") (pinfunction "PGND_PAD") (pintype "passive"))
      (node (ref "IC2") (pin "4") (pinfunction "GND_4") (pintype "bidirectional"))
      (node (ref "LED1") (pin "1") (pinfunction "K_1") (pintype "bidirectional"))
      (node (ref "Q1") (pin "3") (pinfunction "S_3") (pintype "bidirectional"))
      (node (ref "Q2") (pin "3") (pinfunction "S_3") (pintype "bidirectional"))
      (node (ref "Q3") (pin "3") (pinfunction "S_3") (pintype "bidirectional"))
      (node (ref "Q4") (pin "3") (pinfunction "S_3") (pintype "bidirectional"))
      (node (ref "Q5") (pin "2") (pinfunction "S_2") (pintype "bidirectional"))
      (node (ref "R1") (pin "2") (pinfunction "2_2") (pintype "passive"))
      (node (ref "R11") (pin "2") (pinfunction "2_2") (pintype "passive"))
      (node (ref "R12") (pin "2") (pinfunction "2_2") (pintype "passive"))
      (node (ref "R13") (pin "1") (pinfunction "1_1") (pintype "passive"))
      (node (ref "R17") (pin "1") (pinfunction "1_1") (pintype "passive"))
      (node (ref "R4") (pin "1") (pinfunction "1_1") (pintype "passive"))
      (node (ref "R6") (pin "2") (pinfunction "2_2") (pintype "passive"))
      (node (ref "R7") (pin "2") (pinfunction "2_2") (pintype "passive"))
      (node (ref "R9") (pin "1") (pinfunction "1_1") (pintype "passive"))
      (node (ref "S1") (pin "2") (pinfunction "COM_2") (pintype "bidirectional"))
      (node (ref "U2") (pin "33") (pinfunction "VDD_PA_IN_33") (pintype "power_in"))
      (node (ref "U2") (pin "39") (pinfunction "VIN_DCDC_PA_39") (pintype "power_in"))
      (node (ref "U2") (pin "65") (pinfunction "GND_TAB_65") (pintype "power_in"))
      (node (ref "U2") (pin "V") (pinfunction "V0_V") (pintype "bidirectional"))
      (node (ref "U2") (pin "V_1") (pinfunction "V1_V_1") (pintype "bidirectional"))
      (node (ref "U2") (pin "V_10") (pinfunction "V10_V_10") (pintype "bidirectional"))
      (node (ref "U2") (pin "V_11") (pinfunction "V11_V_11") (pintype "bidirectional"))
      (node (ref "U2") (pin "V_12") (pinfunction "V12_V_12") (pintype "bidirectional"))
      (node (ref "U2") (pin "V_13") (pinfunction "V13_V_13") (pintype "bidirectional"))
      (node (ref "U2") (pin "V_14") (pinfunction "V14_V_14") (pintype "bidirectional"))
      (node (ref "U2") (pin "V_15") (pinfunction "V15_V_15") (pintype "bidirectional"))
      (node (ref "U2") (pin "V_16") (pinfunction "V16_V_16") (pintype "bidirectional"))
      (node (ref "U2") (pin "V_17") (pinfunction "V17_V_17") (pintype "bidirectional"))
      (node (ref "U2") (pin "V_18") (pinfunction "V18_V_18") (pintype "bidirectional"))
      (node (ref "U2") (pin "V_19") (pinfunction "V19_V_19") (pintype "bidirectional"))
      (node (ref "U2") (pin "V_2") (pinfunction "V2_V_2") (pintype "bidirectional"))
      (node (ref "U2") (pin "V_20") (pinfunction "V20_V_20") (pintype "bidirectional"))
      (node (ref "U2") (pin "V_21") (pinfunction "V21_V_21") (pintype "bidirectional"))
      (node (ref "U2") (pin "V_22") (pinfunction "V22_V_22") (pintype "bidirectional"))
      (node (ref "U2") (pin "V_23") (pinfunction "V23_V_23") (pintype "bidirectional"))
      (node (ref "U2") (pin "V_24") (pinfunction "V24_V_24") (pintype "bidirectional"))
      (node (ref "U2") (pin "V_25") (pinfunction "V25_V_25") (pintype "bidirectional"))
      (node (ref "U2") (pin "V_26") (pinfunction "V26_V_26") (pintype "bidirectional"))
      (node (ref "U2") (pin "V_27") (pinfunction "V27_V_27") (pintype "bidirectional"))
      (node (ref "U2") (pin "V_28") (pinfunction "V28_V_28") (pintype "bidirectional"))
      (node (ref "U2") (pin "V_29") (pinfunction "V29_V_29") (pintype "bidirectional"))
      (node (ref "U2") (pin "V_3") (pinfunction "V3_V_3") (pintype "bidirectional"))
      (node (ref "U2") (pin "V_30") (pinfunction "V30_V_30") (pintype "bidirectional"))
      (node (ref "U2") (pin "V_31") (pinfunction "V31_V_31") (pintype "bidirectional"))
      (node (ref "U2") (pin "V_32") (pinfunction "V32_V_32") (pintype "bidirectional"))
      (node (ref "U2") (pin "V_33") (pinfunction "V33_V_33") (pintype "bidirectional"))
      (node (ref "U2") (pin "V_34") (pinfunction "V34_V_34") (pintype "bidirectional"))
      (node (ref "U2") (pin "V_35") (pinfunction "V35_V_35") (pintype "bidirectional"))
      (node (ref "U2") (pin "V_36") (pinfunction "V36_V_36") (pintype "bidirectional"))
      (node (ref "U2") (pin "V_37") (pinfunction "V37_V_37") (pintype "bidirectional"))
      (node (ref "U2") (pin "V_38") (pinfunction "V38_V_38") (pintype "bidirectional"))
      (node (ref "U2") (pin "V_39") (pinfunction "V39_V_39") (pintype "bidirectional"))
      (node (ref "U2") (pin "V_4") (pinfunction "V4_V_4") (pintype "bidirectional"))
      (node (ref "U2") (pin "V_40") (pinfunction "V40_V_40") (pintype "bidirectional"))
      (node (ref "U2") (pin "V_41") (pinfunction "V41_V_41") (pintype "bidirectional"))
      (node (ref "U2") (pin "V_42") (pinfunction "V42_V_42") (pintype "bidirectional"))
      (node (ref "U2") (pin "V_43") (pinfunction "V43_V_43") (pintype "bidirectional"))
      (node (ref "U2") (pin "V_44") (pinfunction "V44_V_44") (pintype "bidirectional"))
      (node (ref "U2") (pin "V_45") (pinfunction "V45_V_45") (pintype "bidirectional"))
      (node (ref "U2") (pin "V_46") (pinfunction "V46_V_46") (pintype "bidirectional"))
      (node (ref "U2") (pin "V_47") (pinfunction "V47_V_47") (pintype "bidirectional"))
      (node (ref "U2") (pin "V_48") (pinfunction "V48_V_48") (pintype "bidirectional"))
      (node (ref "U2") (pin "V_5") (pinfunction "V5_V_5") (pintype "bidirectional"))
      (node (ref "U2") (pin "V_6") (pinfunction "V6_V_6") (pintype "bidirectional"))
      (node (ref "U2") (pin "V_7") (pinfunction "V7_V_7") (pintype "bidirectional"))
      (node (ref "U2") (pin "V_8") (pinfunction "V8_V_8") (pintype "bidirectional"))
      (node (ref "U2") (pin "V_9") (pinfunction "V9_V_9") (pintype "bidirectional"))
      (node (ref "U3") (pin "P1") (pinfunction "GND1_P1") (pintype "bidirectional"))
      (node (ref "U3") (pin "P10") (pinfunction "AI_0_P10") (pintype "bidirectional"))
      (node (ref "U3") (pin "P11") (pinfunction "GND2_P11") (pintype "bidirectional"))
      (node (ref "U3") (pin "P16") (pinfunction "TDI_P16") (pintype "bidirectional"))
      (node (ref "U3") (pin "P18") (pinfunction "TMS_P18") (pintype "bidirectional"))
      (node (ref "U3") (pin "P20") (pinfunction "GND3_P20") (pintype "bidirectional"))
      (node (ref "U3") (pin "P30") (pinfunction "GND4_P30") (pintype "bidirectional"))
      (node (ref "U3") (pin "P34") (pinfunction "GND5_P34") (pintype "bidirectional"))
      (node (ref "U3") (pin "P37") (pinfunction "GND6_P37") (pintype "bidirectional"))
      (node (ref "U3") (pin "P42") (pinfunction "GND7_P42") (pintype "bidirectional"))
      (node (ref "U3") (pin "P49") (pinfunction "SPIS_SCK/SCL_P49") (pintype "bidirectional"))
      (node (ref "U3") (pin "P56") (pinfunction "GND8_P56") (pintype "bidirectional"))
      (node (ref "U3") (pin "P57") (pinfunction "UART_RX_RTSN_P57") (pintype "bidirectional"))
      (node (ref "U3") (pin "P59") (pinfunction "UART_RX_P59") (pintype "bidirectional"))
      (node (ref "U3") (pin "P64") (pinfunction "RADIO_INHIBIT_P64") (pintype "bidirectional"))
      (node (ref "U3") (pin "P66") (pinfunction "GND9_P66") (pintype "bidirectional"))
      (node (ref "U3") (pin "P7") (pinfunction "AI_2_P7") (pintype "bidirectional"))
      (node (ref "U3") (pin "P8") (pinfunction "AI_1_P8") (pintype "bidirectional"))
      (node (ref "U3") (pin "P9") (pinfunction "AI_3_P9") (pintype "bidirectional"))
    )
    (net (code "16") (name "GPIO2") (class "Default")
      (node (ref "U2") (pin "57") (pinfunction "GPIO2_57") (pintype "bidirectional"))
      (node (ref "U4") (pin "P$4") (pinfunction "TMP_P$4") (pintype "bidirectional"))
    )
    (net (code "17") (name "GPIO3") (class "Default")
      (node (ref "U2") (pin "58") (pinfunction "GPIO3_58") (pintype "bidirectional"))
      (node (ref "U4") (pin "P$3") (pinfunction "RV_P$3") (pintype "bidirectional"))
    )
    (net (code "18") (name "GPIO4") (class "Default")
      (node (ref "U2") (pin "59") (pinfunction "GPIO4_59") (pintype "bidirectional"))
      (node (ref "U5") (pin "P$2") (pinfunction "SIG_P$2") (pintype "bidirectional"))
    )
    (net (code "19") (name "GPIO5") (class "Default")
      (node (ref "U2") (pin "60") (pinfunction "GPIO5_60") (pintype "bidirectional"))
      (node (ref "U6") (pin "P$2") (pinfunction "SIG_P$2") (pintype "bidirectional"))
    )
    (net (code "20") (name "GPIO12") (class "Default")
      (node (ref "Q4") (pin "1") (pinfunction "G_1") (pintype "bidirectional"))
      (node (ref "U2") (pin "3") (pinfunction "GPIO12_3") (pintype "bidirectional"))
    )
    (net (code "21") (name "GPIO13") (class "Default")
      (node (ref "Q1") (pin "1") (pinfunction "G_1") (pintype "bidirectional"))
      (node (ref "U2") (pin "4") (pinfunction "GPIO13_4") (pintype "bidirectional"))
    )
    (net (code "22") (name "GPIO14") (class "Default")
      (node (ref "Q2") (pin "1") (pinfunction "G_1") (pintype "bidirectional"))
      (node (ref "U2") (pin "5") (pinfunction "GPIO14_5") (pintype "bidirectional"))
    )
    (net (code "23") (name "GPIO15") (class "Default")
      (node (ref "Q3") (pin "1") (pinfunction "G_1") (pintype "bidirectional"))
      (node (ref "U2") (pin "6") (pinfunction "GPIO15_6") (pintype "bidirectional"))
    )
    (net (code "24") (name "GPIO22") (class "Default")
      (node (ref "IC1") (pin "3") (pinfunction "EN_3") (pintype "passive"))
      (node (ref "U2") (pin "15") (pinfunction "GPIO22_15") (pintype "bidirectional"))
    )
    (net (code "25") (name "GPIO31") (class "Default")
      (node (ref "JP2") (pin "2") (pinfunction "2_2") (pintype "passive"))
    )
    (net (code "26") (name "IPCS_MISO") (class "Default")
      (node (ref "HDR1") (pin "5") (pinfunction "5_5") (pintype "bidirectional"))
      (node (ref "U3") (pin "P33") (pinfunction "IPCS_MISO_P33") (pintype "bidirectional"))
    )
    (net (code "27") (name "IPCS_MOSI") (class "Default")
      (node (ref "HDR1") (pin "4") (pinfunction "4_4") (pintype "bidirectional"))
      (node (ref "U3") (pin "P35") (pinfunction "IPCS_MOSI_P35") (pintype "bidirectional"))
    )
    (net (code "28") (name "IPCS_SCK") (class "Default")
      (node (ref "HDR1") (pin "3") (pinfunction "3_3") (pintype "bidirectional"))
      (node (ref "U3") (pin "P36") (pinfunction "IPCS_SCK_P36") (pintype "bidirectional"))
    )
    (net (code "29") (name "IPCS_SSN") (class "Default")
      (node (ref "HDR1") (pin "1") (pinfunction "1_1") (pintype "bidirectional"))
      (node (ref "U3") (pin "P39") (pinfunction "IPCS_SSN_P39") (pintype "bidirectional"))
    )
    (net (code "30") (name "Net-(AC1-GND_1)") (class "Default")
      (node (ref "AC1") (pin "2") (pinfunction "GND_1_2") (pintype "power_in"))
      (node (ref "AC1") (pin "4") (pinfunction "GND_2_4") (pintype "power_in"))
      (node (ref "AC1") (pin "5") (pinfunction "GND_3_5") (pintype "power_in"))
      (node (ref "Q1") (pin "2") (pinfunction "D_2") (pintype "bidirectional"))
      (node (ref "U6") (pin "P$3") (pinfunction "GND_P$3") (pintype "power_in"))
      (node (ref "X1") (pin "4") (pinfunction "4_4") (pintype "bidirectional"))
      (node (ref "X2") (pin "4") (pinfunction "4_4") (pintype "bidirectional"))
    )
    (net (code "31") (name "Net-(D2-A)") (class "Default")
      (node (ref "D2") (pin "2") (pinfunction "A_2") (pintype "bidirectional"))
      (node (ref "R16") (pin "1") (pinfunction "1_1") (pintype "passive"))
    )
    (net (code "32") (name "Net-(IC1-FB)") (class "Default")
      (node (ref "C7") (pin "1") (pinfunction "1_1") (pintype "passive"))
      (node (ref "IC1") (pin "8") (pinfunction "FB_8") (pintype "passive"))
      (node (ref "R4") (pin "2") (pinfunction "2_2") (pintype "passive"))
      (node (ref "R5") (pin "1") (pinfunction "1_1") (pintype "passive"))
    )
    (net (code "33") (name "Net-(IC1-L1)") (class "Default")
      (node (ref "IC1") (pin "1") (pinfunction "L1_1") (pintype "passive"))
      (node (ref "L1") (pin "2") (pinfunction "2_2") (pintype "passive"))
    )
    (net (code "34") (name "Net-(IC1-L2)") (class "Default")
      (node (ref "IC1") (pin "10") (pinfunction "L2_10") (pintype "passive"))
      (node (ref "L1") (pin "1") (pinfunction "1_1") (pintype "passive"))
    )
    (net (code "35") (name "Net-(IC1-PG)") (class "Default")
      (node (ref "IC1") (pin "5") (pinfunction "PG_5") (pintype "passive"))
      (node (ref "R3") (pin "1") (pinfunction "1_1") (pintype "passive"))
    )
    (net (code "36") (name "Net-(IC1-VAUX)") (class "Default")
      (node (ref "C6") (pin "1") (pinfunction "1_1") (pintype "passive"))
      (node (ref "IC1") (pin "6") (pinfunction "VAUX_6") (pintype "passive"))
    )
    (net (code "37") (name "Net-(JP1-Pad1)") (class "Default")
      (node (ref "JP1") (pin "1") (pinfunction "1_1") (pintype "passive"))
      (node (ref "JP1") (pin "3") (pinfunction "3_3") (pintype "passive"))
      (node (ref "JP1") (pin "5") (pinfunction "5_5") (pintype "passive"))
      (node (ref "R2") (pin "1") (pinfunction "1_1") (pintype "passive"))
    )
    (net (code "38") (name "Net-(LED1-A)") (class "Default")
      (node (ref "LED1") (pin "2") (pinfunction "A_2") (pintype "bidirectional"))
      (node (ref "R10") (pin "2") (pinfunction "2_2") (pintype "passive"))
    )
    (net (code "39") (name "Net-(PB2-Pad2)") (class "Default")
      (node (ref "PB2") (pin "2") (pinfunction "2_2") (pintype "bidirectional"))
      (node (ref "R17") (pin "2") (pinfunction "2_2") (pintype "passive"))
    )
    (net (code "40") (name "Net-(Q2-D)") (class "Default")
      (node (ref "Q2") (pin "2") (pinfunction "D_2") (pintype "bidirectional"))
      (node (ref "U4") (pin "P$2") (pinfunction "GND_P$2") (pintype "power_in"))
    )
    (net (code "41") (name "Net-(Q3-D)") (class "Default")
      (node (ref "Q3") (pin "2") (pinfunction "D_2") (pintype "bidirectional"))
      (node (ref "U5") (pin "P$3") (pinfunction "GND_P$3") (pintype "power_in"))
    )
    (net (code "42") (name "Net-(Q4-D)") (class "Default")
      (node (ref "Q4") (pin "2") (pinfunction "D_2") (pintype "bidirectional"))
      (node (ref "X3") (pin "4") (pinfunction "4_4") (pintype "bidirectional"))
    )
    (net (code "43") (name "Net-(U2-DCDC_ANA_SW)") (class "Default")
      (node (ref "L2") (pin "2") (pinfunction "2_2") (pintype "passive"))
      (node (ref "U2") (pin "38") (pinfunction "DCDC_ANA_SW_38") (pintype "power_in"))
    )
    (net (code "44") (name "Net-(U2-RTC_XTAL_N)") (class "Default")
      (node (ref "C10") (pin "1") (pinfunction "1_1") (pintype "passive"))
      (node (ref "U2") (pin "52") (pinfunction "RTC_XTAL_N_52") (pintype "passive"))
      (node (ref "Y1") (pin "1") (pinfunction "1_1") (pintype "passive"))
    )
    (net (code "45") (name "Net-(U2-RTC_XTAL_P)") (class "Default")
      (node (ref "C11") (pin "1") (pinfunction "1_1") (pintype "passive"))
      (node (ref "U2") (pin "51") (pinfunction "RTC_XTAL_P_51") (pintype "passive"))
      (node (ref "Y1") (pin "3") (pinfunction "2_3") (pintype "passive"))
    )
    (net (code "46") (name "Net-(U2-VDD_PLL)") (class "Default")
      (node (ref "C5") (pin "1") (pinfunction "1_1") (pintype "passive"))
      (node (ref "U2") (pin "24") (pinfunction "VDD_PLL_24") (pintype "power_in"))
    )
    (net (code "47") (name "Net-(U2-VDD_RAM)") (class "Default")
      (node (ref "C4") (pin "1") (pinfunction "1_1") (pintype "passive"))
      (node (ref "U2") (pin "49") (pinfunction "VDD_RAM_49") (pintype "power_in"))
    )
    (net (code "48") (name "RESETN") (class "Default")
      (node (ref "HDR1") (pin "6") (pinfunction "6_6") (pintype "bidirectional"))
      (node (ref "Q5") (pin "3") (pinfunction "D_3") (pintype "bidirectional"))
      (node (ref "U3") (pin "P15") (pinfunction "RESETN_P15") (pintype "bidirectional"))
    )
    (net (code "49") (name "RST_BTN") (class "Default")
      (node (ref "C13") (pin "1") (pinfunction "1_1") (pintype "passive"))
      (node (ref "PB1") (pin "1") (pinfunction "1_1") (pintype "bidirectional"))
      (node (ref "Q5") (pin "1") (pinfunction "G_1") (pintype "bidirectional"))
      (node (ref "R9") (pin "2") (pinfunction "2_2") (pintype "passive"))
    )
    (net (code "50") (name "SCL") (class "Default")
      (node (ref "AC1") (pin "14") (pinfunction "SCL/SCLK_14") (pintype "input"))
      (node (ref "R14") (pin "2") (pinfunction "2_2") (pintype "passive"))
      (node (ref "U2") (pin "1") (pinfunction "GPIO10_1") (pintype "bidirectional"))
      (node (ref "X1") (pin "2") (pinfunction "2_2") (pintype "power_in"))
      (node (ref "X2") (pin "2") (pinfunction "2_2") (pintype "power_in"))
      (node (ref "X3") (pin "2") (pinfunction "2_2") (pintype "power_in"))
    )
    (net (code "51") (name "SDA") (class "Default")
      (node (ref "AC1") (pin "13") (pinfunction "SDA/SDI/SDIO_13") (pintype "bidirectional"))
      (node (ref "R15") (pin "2") (pinfunction "2_2") (pintype "passive"))
      (node (ref "U2") (pin "2") (pinfunction "GPIO11_2") (pintype "bidirectional"))
      (node (ref "X1") (pin "3") (pinfunction "3_3") (pintype "bidirectional"))
      (node (ref "X2") (pin "3") (pinfunction "3_3") (pintype "bidirectional"))
      (node (ref "X3") (pin "3") (pinfunction "3_3") (pintype "bidirectional"))
    )
    (net (code "52") (name "SOP0") (class "Default")
      (node (ref "JP1") (pin "6") (pinfunction "6_6") (pintype "passive"))
      (node (ref "R12") (pin "1") (pinfunction "1_1") (pintype "passive"))
      (node (ref "U2") (pin "35") (pinfunction "SOP0_35") (pintype "input"))
    )
    (net (code "53") (name "SOP1") (class "Default")
      (node (ref "JP1") (pin "4") (pinfunction "4_4") (pintype "passive"))
      (node (ref "R11") (pin "1") (pinfunction "1_1") (pintype "passive"))
      (node (ref "U2") (pin "34") (pinfunction "SOP1_34") (pintype "input"))
    )
    (net (code "54") (name "SOP2") (class "Default")
      (node (ref "JP1") (pin "2") (pinfunction "2_2") (pintype "passive"))
      (node (ref "R13") (pin "2") (pinfunction "2_2") (pintype "passive"))
      (node (ref "U2") (pin "21") (pinfunction "SOP2_21") (pintype "output"))
    )
    (net (code "55") (name "TCK") (class "Default")
      (node (ref "CN1") (pin "4") (pinfunction "4_4") (pintype "bidirectional"))
      (node (ref "R1") (pin "1") (pinfunction "1_1") (pintype "passive"))
      (node (ref "U2") (pin "19") (pinfunction "TCK_19") (pintype "bidirectional"))
    )
    (net (code "56") (name "TDI") (class "Default")
      (node (ref "CN1") (pin "2") (pinfunction "2_2") (pintype "bidirectional"))
      (node (ref "U2") (pin "16") (pinfunction "TDI_16") (pintype "bidirectional"))
    )
    (net (code "57") (name "TDO") (class "Default")
      (node (ref "CN1") (pin "1") (pinfunction "1_1") (pintype "bidirectional"))
      (node (ref "U2") (pin "17") (pinfunction "TDO_17") (pintype "bidirectional"))
    )
    (net (code "58") (name "TMS") (class "Default")
      (node (ref "CN1") (pin "3") (pinfunction "3_3") (pintype "bidirectional"))
      (node (ref "U2") (pin "20") (pinfunction "TMS_20") (pintype "bidirectional"))
    )
    (net (code "59") (name "UARTC0_RX") (class "Default")
      (node (ref "HDR1") (pin "10") (pinfunction "10_10") (pintype "bidirectional"))
      (node (ref "U2") (pin "8") (pinfunction "GPIO17_8") (pintype "bidirectional"))
      (node (ref "U3") (pin "P32") (pinfunction "UARTC0_RX_P32") (pintype "bidirectional"))
    )
    (net (code "60") (name "UARTC0_TX") (class "Default")
      (node (ref "HDR1") (pin "9") (pinfunction "9_9") (pintype "bidirectional"))
      (node (ref "U2") (pin "7") (pinfunction "GPIO16_7") (pintype "bidirectional"))
      (node (ref "U3") (pin "P31") (pinfunction "UARTC0_TX_P31") (pintype "bidirectional"))
    )
    (net (code "61") (name "VCC_DCDC") (class "Default")
      (node (ref "JP3") (pin "2") (pinfunction "2_2") (pintype "passive"))
    )
    (net (code "62") (name "VDD_ANA1") (class "Default")
      (node (ref "C19") (pin "1") (pinfunction "1_1") (pintype "passive"))
      (node (ref "C20") (pin "1") (pinfunction "1_1") (pintype "passive"))
      (node (ref "C21") (pin "1") (pinfunction "1_1") (pintype "passive"))
      (node (ref "C22") (pin "1") (pinfunction "1_1") (pintype "passive"))
      (node (ref "L2") (pin "1") (pinfunction "1_1") (pintype "passive"))
      (node (ref "U2") (pin "25") (pinfunction "LDO_IN2_25") (pintype "power_in"))
      (node (ref "U2") (pin "36") (pinfunction "LDO_IN1_36") (pintype "power_in"))
      (node (ref "U2") (pin "48") (pinfunction "VDD_ANA1_48") (pintype "power_in"))
    )
    (net (code "63") (name "VDD_ANA2") (class "Default")
      (node (ref "JP3") (pin "1") (pinfunction "1_1") (pintype "passive"))
      (node (ref "U2") (pin "47") (pinfunction "VDD_ANA2_47") (pintype "power_in"))
    )
    (net (code "64") (name "VDD_DIG") (class "Default")
      (node (ref "C16") (pin "1") (pinfunction "1_1") (pintype "passive"))
      (node (ref "C17") (pin "1") (pinfunction "1_1") (pintype "passive"))
      (node (ref "C18") (pin "1") (pinfunction "1_1") (pintype "passive"))
      (node (ref "L3") (pin "1") (pinfunction "1_1") (pintype "passive"))
      (node (ref "U2") (pin "56") (pinfunction "VDD_DIG2_56") (pintype "power_in"))
      (node (ref "U2") (pin "9") (pinfunction "VDD_DIG1_9") (pintype "power_in"))
    )
    (net (code "65") (name "unconnected-(AC1-INT1-Pad8)") (class "Default")
      (node (ref "AC1") (pin "8") (pinfunction "INT1_8") (pintype "input"))
    )
    (net (code "66") (name "unconnected-(AC1-INT2-Pad9)") (class "Default")
      (node (ref "AC1") (pin "9") (pinfunction "INT2_9") (pintype "input"))
    )
    (net (code "67") (name "unconnected-(AC1-NC-Pad10)") (class "Default")
      (node (ref "AC1") (pin "10") (pinfunction "NC_10") (pintype "no_connect"))
    )
    (net (code "68") (name "unconnected-(AC1-RESERVED_1-Pad3)") (class "Default")
      (node (ref "AC1") (pin "3") (pinfunction "RESERVED_1_3") (pintype "bidirectional"))
    )
    (net (code "69") (name "unconnected-(AC1-RESERVED_2-Pad11)") (class "Default")
      (node (ref "AC1") (pin "11") (pinfunction "RESERVED_2_11") (pintype "bidirectional"))
    )
    (net (code "70") (name "unconnected-(AC1-SDO{slash}ALT_ADDRESS-Pad12)") (class "Default")
      (node (ref "AC1") (pin "12") (pinfunction "SDO/ALT_ADDRESS_12") (pintype "bidirectional"))
    )
    (net (code "71") (name "unconnected-(AC1-VS-Pad6)") (class "Default")
      (node (ref "AC1") (pin "6") (pinfunction "VS_6") (pintype "bidirectional"))
    )
    (net (code "72") (name "unconnected-(AC1-~{CS}-Pad7)") (class "Default")
      (node (ref "AC1") (pin "7") (pinfunction "~{CS}_7") (pintype "input"))
    )
    (net (code "73") (name "unconnected-(D1-NC-Pad3)") (class "Default")
      (node (ref "D1") (pin "3") (pinfunction "NC_3") (pintype "no_connect"))
    )
    (net (code "74") (name "unconnected-(S1-NC-Pad3)") (class "Default")
      (node (ref "S1") (pin "3") (pinfunction "NC_3") (pintype "no_connect"))
    )
    (net (code "75") (name "unconnected-(S1-PadMH1)") (class "Default")
      (node (ref "S1") (pin "MH1") (pinfunction "MH1_MH1") (pintype "bidirectional"))
    )
    (net (code "76") (name "unconnected-(S1-PadMH2)") (class "Default")
      (node (ref "S1") (pin "MH2") (pinfunction "MH2_MH2") (pintype "bidirectional"))
    )
    (net (code "77") (name "unconnected-(S1-PadMH3)") (class "Default")
      (node (ref "S1") (pin "MH3") (pinfunction "MH3_MH3") (pintype "bidirectional"))
    )
    (net (code "78") (name "unconnected-(S1-PadMH4)") (class "Default")
      (node (ref "S1") (pin "MH4") (pinfunction "MH4_MH4") (pintype "bidirectional"))
    )
    (net (code "79") (name "unconnected-(U2-ANTSEL1-Pad29)") (class "Default")
      (node (ref "U2") (pin "29") (pinfunction "ANTSEL1_29") (pintype "output"))
    )
    (net (code "80") (name "unconnected-(U2-ANTSEL2-Pad30)") (class "Default")
      (node (ref "U2") (pin "30") (pinfunction "ANTSEL2_30") (pintype "output"))
    )
    (net (code "81") (name "unconnected-(U2-DCDC_ANA2_SW_P-Pad45)") (class "Default")
      (node (ref "U2") (pin "45") (pinfunction "DCDC_ANA2_SW_P_45") (pintype "bidirectional"))
    )
    (net (code "82") (name "unconnected-(U2-GPIO0-Pad50)") (class "Default")
      (node (ref "U2") (pin "50") (pinfunction "GPIO0_50") (pintype "bidirectional"))
    )
    (net (code "83") (name "unconnected-(U2-GPIO1-Pad55)") (class "Default")
      (node (ref "U2") (pin "55") (pinfunction "GPIO1_55") (pintype "bidirectional"))
    )
    (net (code "84") (name "unconnected-(U2-GPIO6-Pad61)") (class "Default")
      (node (ref "U2") (pin "61") (pinfunction "GPIO6_61") (pintype "bidirectional"))
    )
    (net (code "85") (name "unconnected-(U2-GPIO7-Pad62)") (class "Default")
      (node (ref "U2") (pin "62") (pinfunction "GPIO7_62") (pintype "bidirectional"))
    )
    (net (code "86") (name "unconnected-(U2-GPIO8-Pad63)") (class "Default")
      (node (ref "U2") (pin "63") (pinfunction "GPIO8_63") (pintype "bidirectional"))
    )
    (net (code "87") (name "unconnected-(U2-GPIO9-Pad64)") (class "Default")
      (node (ref "U2") (pin "64") (pinfunction "GPIO9_64") (pintype "bidirectional"))
    )
    (net (code "88") (name "unconnected-(U2-GPIO28-Pad18)") (class "Default")
      (node (ref "U2") (pin "18") (pinfunction "GPIO28_18") (pintype "bidirectional"))
    )
    (net (code "89") (name "unconnected-(U2-GPIO30-Pad53)") (class "Default")
      (node (ref "U2") (pin "53") (pinfunction "GPIO30_53") (pintype "bidirectional"))
    )
    (net (code "90") (name "unconnected-(U2-NC-Pad28)") (class "Default")
      (node (ref "U2") (pin "28") (pinfunction "NC_28") (pintype "passive"))
    )
    (net (code "91") (name "unconnected-(U2-NC_2-Pad26)") (class "Default")
      (node (ref "U2") (pin "26") (pinfunction "NC_2_26") (pintype "passive"))
    )
    (net (code "92") (name "unconnected-(U2-NC_3-Pad27)") (class "Default")
      (node (ref "U2") (pin "27") (pinfunction "NC_3_27") (pintype "passive"))
    )
    (net (code "93") (name "unconnected-(U2-RF_BG-Pad31)") (class "Default")
      (node (ref "U2") (pin "31") (pinfunction "RF_BG_31") (pintype "passive"))
    )
    (net (code "94") (name "unconnected-(U2-WLAN_XTAL_N-Pad22)") (class "Default")
      (node (ref "U2") (pin "22") (pinfunction "WLAN_XTAL_N_22") (pintype "passive"))
    )
    (net (code "95") (name "unconnected-(U2-WLAN_XTAL_P-Pad23)") (class "Default")
      (node (ref "U2") (pin "23") (pinfunction "WLAN_XTAL_P_23") (pintype "passive"))
    )
    (net (code "96") (name "unconnected-(U3-GPIO17-PadP4)") (class "Default")
      (node (ref "U3") (pin "P4") (pinfunction "GPIO17_P4") (pintype "bidirectional"))
    )
    (net (code "97") (name "unconnected-(U3-GPIO18-PadP5)") (class "Default")
      (node (ref "U3") (pin "P5") (pinfunction "GPIO18_P5") (pintype "bidirectional"))
    )
    (net (code "98") (name "unconnected-(U3-GPIO19-PadP6)") (class "Default")
      (node (ref "U3") (pin "P6") (pinfunction "GPIO19_P6") (pintype "bidirectional"))
    )
    (net (code "99") (name "unconnected-(U3-GPIO23-PadP21)") (class "Default")
      (node (ref "U3") (pin "P21") (pinfunction "GPIO23_P21") (pintype "bidirectional"))
    )
    (net (code "100") (name "unconnected-(U3-LPTIMER_EXT-PadP26)") (class "Default")
      (node (ref "U3") (pin "P26") (pinfunction "LPTIMER_EXT_P26") (pintype "bidirectional"))
    )
    (net (code "101") (name "unconnected-(U3-NC1-PadP3)") (class "Default")
      (node (ref "U3") (pin "P3") (pinfunction "NC1_P3") (pintype "bidirectional"))
    )
    (net (code "102") (name "unconnected-(U3-NC2-PadP13)") (class "Default")
      (node (ref "U3") (pin "P13") (pinfunction "NC2_P13") (pintype "bidirectional"))
    )
    (net (code "103") (name "unconnected-(U3-NC3-PadP14)") (class "Default")
      (node (ref "U3") (pin "P14") (pinfunction "NC3_P14") (pintype "bidirectional"))
    )
    (net (code "104") (name "unconnected-(U3-NC4-PadP29)") (class "Default")
      (node (ref "U3") (pin "P29") (pinfunction "NC4_P29") (pintype "bidirectional"))
    )
    (net (code "105") (name "unconnected-(U3-NC5-PadP52)") (class "Default")
      (node (ref "U3") (pin "P52") (pinfunction "NC5_P52") (pintype "bidirectional"))
    )
    (net (code "106") (name "unconnected-(U3-NC6-PadP53)") (class "Default")
      (node (ref "U3") (pin "P53") (pinfunction "NC6_P53") (pintype "bidirectional"))
    )
    (net (code "107") (name "unconnected-(U3-NC7-PadP65)") (class "Default")
      (node (ref "U3") (pin "P65") (pinfunction "NC7_P65") (pintype "bidirectional"))
    )
    (net (code "108") (name "unconnected-(U3-P$2-PadP2)") (class "Default")
      (node (ref "U3") (pin "P2") (pinfunction "P$2_P2") (pintype "bidirectional"))
    )
    (net (code "109") (name "unconnected-(U3-P$12-PadP12)") (class "Default")
      (node (ref "U3") (pin "P12") (pinfunction "P$12_P12") (pintype "bidirectional"))
    )
    (net (code "110") (name "unconnected-(U3-P$22-PadP22)") (class "Default")
      (node (ref "U3") (pin "P22") (pinfunction "P$22_P22") (pintype "bidirectional"))
    )
    (net (code "111") (name "unconnected-(U3-P$23-PadP23)") (class "Default")
      (node (ref "U3") (pin "P23") (pinfunction "P$23_P23") (pintype "bidirectional"))
    )
    (net (code "112") (name "unconnected-(U3-P$24-PadP24)") (class "Default")
      (node (ref "U3") (pin "P24") (pinfunction "P$24_P24") (pintype "bidirectional"))
    )
    (net (code "113") (name "unconnected-(U3-P$54-PadP54)") (class "Default")
      (node (ref "U3") (pin "P54") (pinfunction "P$54_P54") (pintype "bidirectional"))
    )
    (net (code "114") (name "unconnected-(U3-PWM0{slash}TIMER16_OUT-PadP46)") (class "Default")
      (node (ref "U3") (pin "P46") (pinfunction "PWM0/TIMER16_OUT_P46") (pintype "bidirectional"))
    )
    (net (code "115") (name "unconnected-(U3-SPIM_MISO-PadP38)") (class "Default")
      (node (ref "U3") (pin "P38") (pinfunction "SPIM_MISO_P38") (pintype "bidirectional"))
    )
    (net (code "116") (name "unconnected-(U3-SPIM_MOSI-PadP40)") (class "Default")
      (node (ref "U3") (pin "P40") (pinfunction "SPIM_MOSI_P40") (pintype "bidirectional"))
    )
    (net (code "117") (name "unconnected-(U3-SPIM_SCK-PadP41)") (class "Default")
      (node (ref "U3") (pin "P41") (pinfunction "SPIM_SCK_P41") (pintype "bidirectional"))
    )
    (net (code "118") (name "unconnected-(U3-SPIM_SS_0N-PadP44)") (class "Default")
      (node (ref "U3") (pin "P44") (pinfunction "SPIM_SS_0N_P44") (pintype "bidirectional"))
    )
    (net (code "119") (name "unconnected-(U3-SPIM_SS_1N-PadP43)") (class "Default")
      (node (ref "U3") (pin "P43") (pinfunction "SPIM_SS_1N_P43") (pintype "bidirectional"))
    )
    (net (code "120") (name "unconnected-(U3-SPIM_SS_2N-PadP28)") (class "Default")
      (node (ref "U3") (pin "P28") (pinfunction "SPIM_SS_2N_P28") (pintype "bidirectional"))
    )
    (net (code "121") (name "unconnected-(U3-SPIS_MISO{slash}UARTC1_TX-PadP47)") (class "Default")
      (node (ref "U3") (pin "P47") (pinfunction "SPIS_MISO/UARTC1_TX_P47") (pintype "bidirectional"))
    )
    (net (code "122") (name "unconnected-(U3-SPIS_MOSI_UARTC1_RX-PadP48)") (class "Default")
      (node (ref "U3") (pin "P48") (pinfunction "SPIS_MOSI_UARTC1_RX_P48") (pintype "bidirectional"))
    )
    (net (code "123") (name "unconnected-(U3-SPIS_SSN{slash}SDA-PadP50)") (class "Default")
      (node (ref "U3") (pin "P50") (pinfunction "SPIS_SSN/SDA_P50") (pintype "bidirectional"))
    )
    (net (code "124") (name "unconnected-(U3-TDO-PadP17)") (class "Default")
      (node (ref "U3") (pin "P17") (pinfunction "TDO_P17") (pintype "bidirectional"))
    )
    (net (code "125") (name "unconnected-(U3-TIMER8_EXT-PadP25)") (class "Default")
      (node (ref "U3") (pin "P25") (pinfunction "TIMER8_EXT_P25") (pintype "bidirectional"))
    )
    (net (code "126") (name "unconnected-(U3-TIMER16_EXT-PadP45)") (class "Default")
      (node (ref "U3") (pin "P45") (pinfunction "TIMER16_EXT_P45") (pintype "bidirectional"))
    )
    (net (code "127") (name "unconnected-(U3-UART_RX_CTSN-PadP58)") (class "Default")
      (node (ref "U3") (pin "P58") (pinfunction "UART_RX_CTSN_P58") (pintype "bidirectional"))
    )
    (net (code "128") (name "unconnected-(U3-UART_TX-PadP62)") (class "Default")
      (node (ref "U3") (pin "P62") (pinfunction "UART_TX_P62") (pintype "bidirectional"))
    )
    (net (code "129") (name "unconnected-(U3-UART_TX_CTSN-PadP61)") (class "Default")
      (node (ref "U3") (pin "P61") (pinfunction "UART_TX_CTSN_P61") (pintype "bidirectional"))
    )
    (net (code "130") (name "unconnected-(U3-UART_TX_RTSN-PadP60)") (class "Default")
      (node (ref "U3") (pin "P60") (pinfunction "UART_TX_RTSN_P60") (pintype "bidirectional"))
    )
  )
)
